# RS-485.net
KiCad netlist of a schematic drawn in Altium Designer
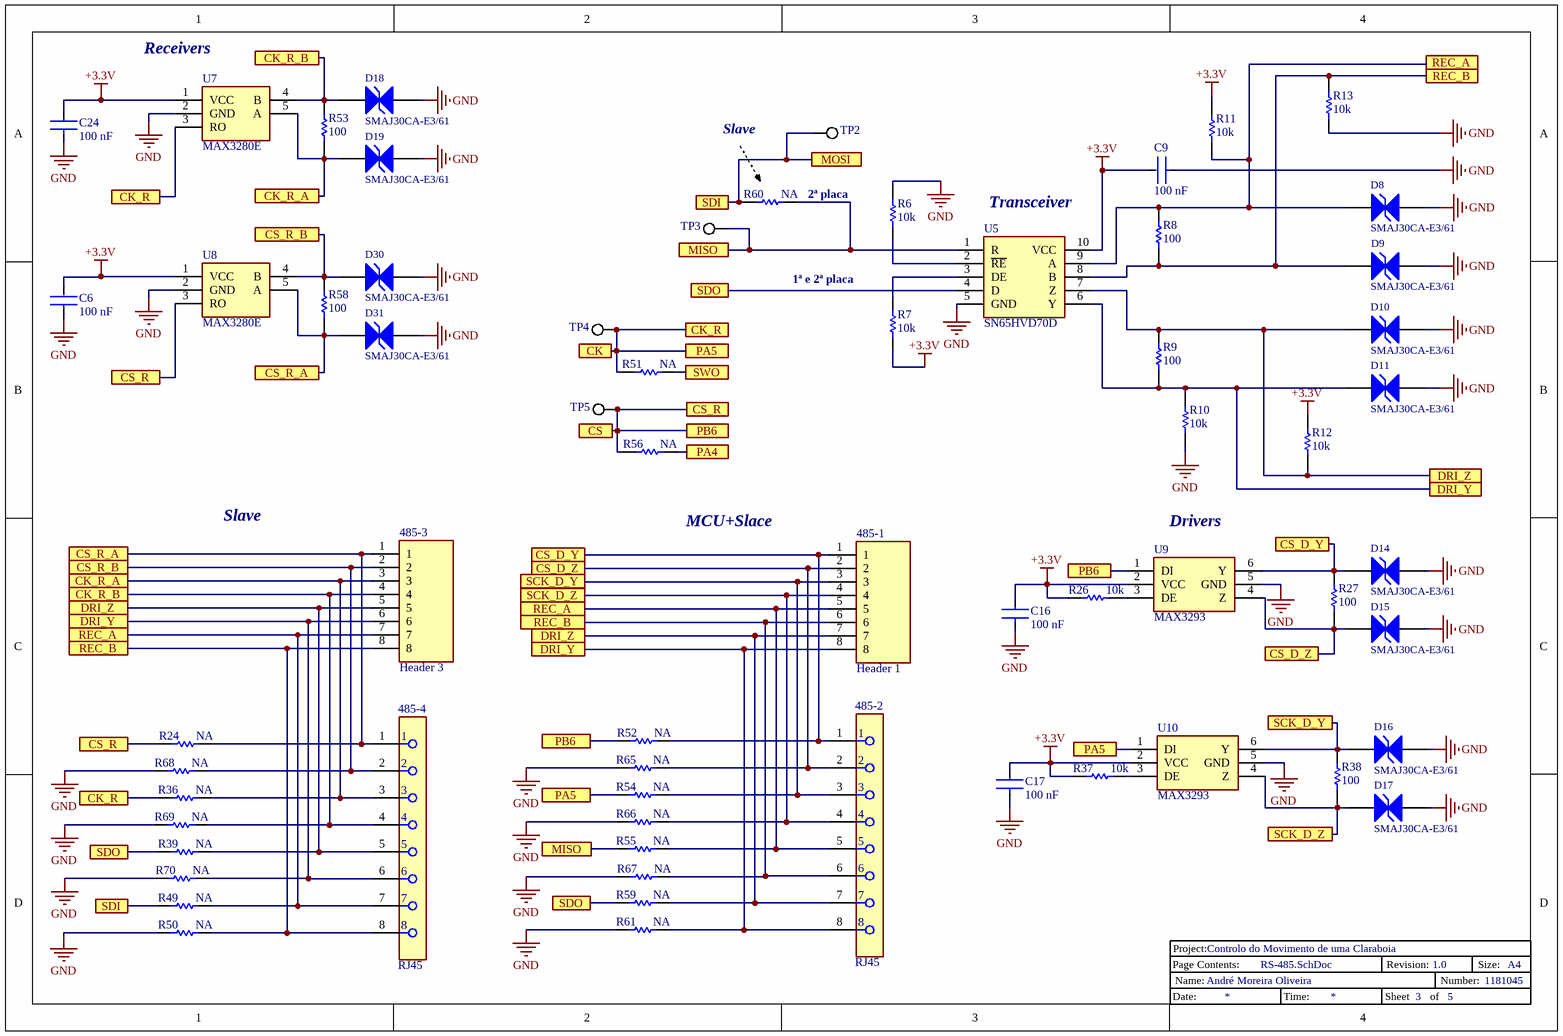
[diagram p0: RS-485.SchDoc]

(export (version "E")
  (design (tool "Eeschema 10.0.6"))
  (components
    (comp (ref "485-1")
      (value "Header 1")
      (footprint "SamacSys:SHDRRA8W64P0X250_1X8_2250X820X420P")
      (description "Conector Femea 1*8 90 graus")
      (fields (field (name "MANUFACTURER_PART_NUMBER") "S8B-EH(LF)(SN)"))
      (libsource (lib "*") (part "S8B-EH_LF__SN_"))
    )
    (comp (ref "485-2")
      (value "RJ45")
      (footprint "FP-RJHSE-5080-MFG")
      (description "CONN MOD JACK 8P8C R/A UNSHLD")
      (fields
        (field (name "MANUFACTURER PART NUMBER") "RJHSE-5080")
        (field (name "OCTOPART") "https://octopart.com/rjhse-5080-amphenol-45060")
      )
      (libsource (lib "Altium Content Vault") (part "b0a0b555dd3abf3683e7c330df25cc4"))
    )
    (comp (ref "485-3")
      (value "Header 3")
      (footprint "SamacSys:SHDRRA8W64P0X250_1X8_2250X820X420P")
      (description "Conector Femea 1*8 90 graus")
      (fields (field (name "MANUFACTURER_PART_NUMBER") "S8B-EH(LF)(SN)"))
      (libsource (lib "*") (part "S8B-EH_LF__SN_"))
    )
    (comp (ref "485-4")
      (value "RJ45")
      (footprint "FP-RJHSE-5080-MFG")
      (description "CONN MOD JACK 8P8C R/A UNSHLD")
      (fields
        (field (name "MANUFACTURER PART NUMBER") "RJHSE-5080")
        (field (name "OCTOPART") "https://octopart.com/rjhse-5080-amphenol-45060")
      )
      (libsource (lib "Altium Content Vault") (part "b0a0b555dd3abf3683e7c330df25cc4"))
    )
    (comp (ref "C6")
      (value "100 nF")
      (footprint "FP-CC0603-DA-MFG")
      (description "CAP CER 0.1UF 50V X7R 0603")
      (fields (field (name "MANUFACTURER") "YAGEO") (field (name "VOLTAGE") "50 V"))
      (libsource (lib "Altium Content Vault") (part "11868f565c42a9108669ba33697ecf6"))
    )
    (comp (ref "C9")
      (value "100 nF")
      (footprint "FP-CC0603-DA-MFG")
      (description "CAP CER 0.1UF 50V X7R 0603")
      (fields (field (name "MANUFACTURER") "YAGEO") (field (name "VOLTAGE") "50 V"))
      (libsource (lib "Altium Content Vault") (part "11868f565c42a9108669ba33697ecf6"))
    )
    (comp (ref "C16")
      (value "100 nF")
      (footprint "FP-CC0603-DA-MFG")
      (description "CAP CER 0.1UF 50V X7R 0603")
      (fields (field (name "MANUFACTURER") "YAGEO") (field (name "VOLTAGE") "50 V"))
      (libsource (lib "Altium Content Vault") (part "11868f565c42a9108669ba33697ecf6"))
    )
    (comp (ref "C17")
      (value "100 nF")
      (footprint "FP-CC0603-DA-MFG")
      (description "CAP CER 0.1UF 50V X7R 0603")
      (fields (field (name "MANUFACTURER") "YAGEO") (field (name "VOLTAGE") "50 V"))
      (libsource (lib "Altium Content Vault") (part "11868f565c42a9108669ba33697ecf6"))
    )
    (comp (ref "C24")
      (value "100 nF")
      (footprint "FP-CC0603-DA-MFG")
      (description "CAP CER 0.1UF 50V X7R 0603")
      (fields (field (name "MANUFACTURER") "YAGEO") (field (name "VOLTAGE") "50 V"))
      (libsource (lib "Altium Content Vault") (part "11868f565c42a9108669ba33697ecf6"))
    )
    (comp (ref "D8")
      (value "SMAJ30CA-E3/61")
      (footprint "VISH-DO-214AC-2_L")
      (fields (field (name "MANUFACTURER") "Vishay Semiconductor"))
      (libsource (lib "Altium Content Vault") (part "VISH-A1A2-2"))
    )
    (comp (ref "D9")
      (value "SMAJ30CA-E3/61")
      (footprint "VISH-DO-214AC-2_L")
      (fields (field (name "MANUFACTURER") "Vishay Semiconductor"))
      (libsource (lib "Altium Content Vault") (part "VISH-A1A2-2"))
    )
    (comp (ref "D10")
      (value "SMAJ30CA-E3/61")
      (footprint "VISH-DO-214AC-2_L")
      (fields (field (name "MANUFACTURER") "Vishay Semiconductor"))
      (libsource (lib "Altium Content Vault") (part "VISH-A1A2-2"))
    )
    (comp (ref "D11")
      (value "SMAJ30CA-E3/61")
      (footprint "VISH-DO-214AC-2_L")
      (fields (field (name "MANUFACTURER") "Vishay Semiconductor"))
      (libsource (lib "Altium Content Vault") (part "VISH-A1A2-2"))
    )
    (comp (ref "D14")
      (value "SMAJ30CA-E3/61")
      (footprint "VISH-DO-214AC-2_L")
      (fields (field (name "MANUFACTURER") "Vishay Semiconductor"))
      (libsource (lib "Altium Content Vault") (part "VISH-A1A2-2"))
    )
    (comp (ref "D15")
      (value "SMAJ30CA-E3/61")
      (footprint "VISH-DO-214AC-2_L")
      (fields (field (name "MANUFACTURER") "Vishay Semiconductor"))
      (libsource (lib "Altium Content Vault") (part "VISH-A1A2-2"))
    )
    (comp (ref "D16")
      (value "SMAJ30CA-E3/61")
      (footprint "VISH-DO-214AC-2_L")
      (fields (field (name "MANUFACTURER") "Vishay Semiconductor"))
      (libsource (lib "Altium Content Vault") (part "VISH-A1A2-2"))
    )
    (comp (ref "D17")
      (value "SMAJ30CA-E3/61")
      (footprint "VISH-DO-214AC-2_L")
      (fields (field (name "MANUFACTURER") "Vishay Semiconductor"))
      (libsource (lib "Altium Content Vault") (part "VISH-A1A2-2"))
    )
    (comp (ref "D18")
      (value "SMAJ30CA-E3/61")
      (footprint "VISH-DO-214AC-2_L")
      (fields (field (name "MANUFACTURER") "Vishay Semiconductor"))
      (libsource (lib "Altium Content Vault") (part "VISH-A1A2-2"))
    )
    (comp (ref "D19")
      (value "SMAJ30CA-E3/61")
      (footprint "VISH-DO-214AC-2_L")
      (fields (field (name "MANUFACTURER") "Vishay Semiconductor"))
      (libsource (lib "Altium Content Vault") (part "VISH-A1A2-2"))
    )
    (comp (ref "D30")
      (value "SMAJ30CA-E3/61")
      (footprint "VISH-DO-214AC-2_L")
      (fields (field (name "MANUFACTURER") "Vishay Semiconductor"))
      (libsource (lib "Altium Content Vault") (part "VISH-A1A2-2"))
    )
    (comp (ref "D31")
      (value "SMAJ30CA-E3/61")
      (footprint "VISH-DO-214AC-2_L")
      (fields (field (name "MANUFACTURER") "Vishay Semiconductor"))
      (libsource (lib "Altium Content Vault") (part "VISH-A1A2-2"))
    )
    (comp (ref "R6")
      (value "10k")
      (footprint "RESC1608X55X25ML10T15")
      (description "Resistor, 10 kOhm, +/- 5%, 100 mW, -55 to 155 degC, 0603 (1608 Metric), RoHS, Tape and Reel")
      (fields (field (name "MANUFACTURER") "Yageo") (field (name "TOLERANCE") "5%"))
      (libsource (lib "Altium Content Vault") (part "RES-2"))
    )
    (comp (ref "R7")
      (value "10k")
      (footprint "RESC1608X55X25ML10T15")
      (description "Resistor, 10 kOhm, +/- 5%, 100 mW, -55 to 155 degC, 0603 (1608 Metric), RoHS, Tape and Reel")
      (fields (field (name "MANUFACTURER") "Yageo") (field (name "TOLERANCE") "5%"))
      (libsource (lib "Altium Content Vault") (part "RES-2"))
    )
    (comp (ref "R8")
      (value "100")
      (footprint "RESC1608X55X25ML10T15")
      (description "Chip Resistor, 100 Ohm, +/- 5%, 0.1 W, -55 to 155 degC, 0603 (1608 Metric), RoHS, Tape and Reel")
      (fields (field (name "TOLERANCE") "5%") (field (name "MANUFACTURER") "Yageo"))
      (libsource (lib "Altium Content Vault") (part "RES-2"))
    )
    (comp (ref "R9")
      (value "100")
      (footprint "RESC1608X55X25ML10T15")
      (description "Chip Resistor, 100 Ohm, +/- 5%, 0.1 W, -55 to 155 degC, 0603 (1608 Metric), RoHS, Tape and Reel")
      (fields (field (name "TOLERANCE") "5%") (field (name "MANUFACTURER") "Yageo"))
      (libsource (lib "Altium Content Vault") (part "RES-2"))
    )
    (comp (ref "R10")
      (value "10k")
      (footprint "RESC1608X55X25ML10T15")
      (description "Resistor, 10 kOhm, +/- 5%, 100 mW, -55 to 155 degC, 0603 (1608 Metric), RoHS, Tape and Reel")
      (fields (field (name "MANUFACTURER") "Yageo") (field (name "TOLERANCE") "5%"))
      (libsource (lib "Altium Content Vault") (part "RES-2"))
    )
    (comp (ref "R11")
      (value "10k")
      (footprint "RESC1608X55X25ML10T15")
      (description "Resistor, 10 kOhm, +/- 5%, 100 mW, -55 to 155 degC, 0603 (1608 Metric), RoHS, Tape and Reel")
      (fields (field (name "MANUFACTURER") "Yageo") (field (name "TOLERANCE") "5%"))
      (libsource (lib "Altium Content Vault") (part "RES-2"))
    )
    (comp (ref "R12")
      (value "10k")
      (footprint "RESC1608X55X25ML10T15")
      (description "Resistor, 10 kOhm, +/- 5%, 100 mW, -55 to 155 degC, 0603 (1608 Metric), RoHS, Tape and Reel")
      (fields (field (name "MANUFACTURER") "Yageo") (field (name "TOLERANCE") "5%"))
      (libsource (lib "Altium Content Vault") (part "RES-2"))
    )
    (comp (ref "R13")
      (value "10k")
      (footprint "RESC1608X55X25ML10T15")
      (description "Resistor, 10 kOhm, +/- 5%, 100 mW, -55 to 155 degC, 0603 (1608 Metric), RoHS, Tape and Reel")
      (fields (field (name "MANUFACTURER") "Yageo") (field (name "TOLERANCE") "5%"))
      (libsource (lib "Altium Content Vault") (part "RES-2"))
    )
    (comp (ref "R24")
      (value "NA")
      (footprint "RESC1608X55X25ML10T15")
      (description "Chip Resistor, 0 Ohm, +/- 5%, 0.1 W, -55 to 155 degC, 0603 (1608 Metric), RoHS, Tape and Reel")
      (fields (field (name "TOLERANCE") "5%") (field (name "MANUFACTURER") "Yageo"))
      (libsource (lib "Altium Content Vault") (part "RES-2"))
    )
    (comp (ref "R26")
      (value "10k")
      (footprint "RESC1608X55X25ML10T15")
      (description "Resistor, 10 kOhm, +/- 5%, 100 mW, -55 to 155 degC, 0603 (1608 Metric), RoHS, Tape and Reel")
      (fields (field (name "MANUFACTURER") "Yageo") (field (name "TOLERANCE") "5%"))
      (libsource (lib "") (part "RES-2_1"))
    )
    (comp (ref "R27")
      (value "100")
      (footprint "RESC1608X55X25ML10T15")
      (description "Chip Resistor, 100 Ohm, +/- 5%, 0.1 W, -55 to 155 degC, 0603 (1608 Metric), RoHS, Tape and Reel")
      (fields (field (name "TOLERANCE") "5%") (field (name "MANUFACTURER") "Yageo"))
      (libsource (lib "Altium Content Vault") (part "RES-2"))
    )
    (comp (ref "R36")
      (value "NA")
      (footprint "RESC1608X55X25ML10T15")
      (description "Chip Resistor, 0 Ohm, +/- 5%, 0.1 W, -55 to 155 degC, 0603 (1608 Metric), RoHS, Tape and Reel")
      (fields (field (name "TOLERANCE") "5%") (field (name "MANUFACTURER") "Yageo"))
      (libsource (lib "Altium Content Vault") (part "RES-2"))
    )
    (comp (ref "R37")
      (value "10k")
      (footprint "RESC1608X55X25ML10T15")
      (description "Resistor, 10 kOhm, +/- 5%, 100 mW, -55 to 155 degC, 0603 (1608 Metric), RoHS, Tape and Reel")
      (fields (field (name "MANUFACTURER") "Yageo") (field (name "TOLERANCE") "5%"))
      (libsource (lib "") (part "RES-2_1"))
    )
    (comp (ref "R38")
      (value "100")
      (footprint "RESC1608X55X25ML10T15")
      (description "Chip Resistor, 100 Ohm, +/- 5%, 0.1 W, -55 to 155 degC, 0603 (1608 Metric), RoHS, Tape and Reel")
      (fields (field (name "TOLERANCE") "5%") (field (name "MANUFACTURER") "Yageo"))
      (libsource (lib "Altium Content Vault") (part "RES-2"))
    )
    (comp (ref "R39")
      (value "NA")
      (footprint "RESC1608X55X25ML10T15")
      (description "Chip Resistor, 0 Ohm, +/- 5%, 0.1 W, -55 to 155 degC, 0603 (1608 Metric), RoHS, Tape and Reel")
      (fields (field (name "TOLERANCE") "5%") (field (name "MANUFACTURER") "Yageo"))
      (libsource (lib "Altium Content Vault") (part "RES-2"))
    )
    (comp (ref "R49")
      (value "NA")
      (footprint "RESC1608X55X25ML10T15")
      (description "Chip Resistor, 0 Ohm, +/- 5%, 0.1 W, -55 to 155 degC, 0603 (1608 Metric), RoHS, Tape and Reel")
      (fields (field (name "TOLERANCE") "5%") (field (name "MANUFACTURER") "Yageo"))
      (libsource (lib "Altium Content Vault") (part "RES-2"))
    )
    (comp (ref "R50")
      (value "NA")
      (footprint "RESC1608X55X25ML10T15")
      (description "Chip Resistor, 0 Ohm, +/- 5%, 0.1 W, -55 to 155 degC, 0603 (1608 Metric), RoHS, Tape and Reel")
      (fields (field (name "TOLERANCE") "5%") (field (name "MANUFACTURER") "Yageo"))
      (libsource (lib "Altium Content Vault") (part "RES-2"))
    )
    (comp (ref "R51")
      (value "NA")
      (footprint "RESC1608X55X25ML10T15")
      (description "Chip Resistor, 0 Ohm, +/- 5%, 0.1 W, -55 to 155 degC, 0603 (1608 Metric), RoHS, Tape and Reel")
      (fields (field (name "TOLERANCE") "5%") (field (name "MANUFACTURER") "Yageo"))
      (libsource (lib "Altium Content Vault") (part "RES-2"))
    )
    (comp (ref "R52")
      (value "NA")
      (footprint "RESC1608X55X25ML10T15")
      (description "Chip Resistor, 0 Ohm, +/- 5%, 0.1 W, -55 to 155 degC, 0603 (1608 Metric), RoHS, Tape and Reel")
      (fields (field (name "TOLERANCE") "5%") (field (name "MANUFACTURER") "Yageo"))
      (libsource (lib "Altium Content Vault") (part "RES-2"))
    )
    (comp (ref "R53")
      (value "100")
      (footprint "RESC1608X55X25ML10T15")
      (description "Chip Resistor, 100 Ohm, +/- 5%, 0.1 W, -55 to 155 degC, 0603 (1608 Metric), RoHS, Tape and Reel")
      (fields (field (name "TOLERANCE") "5%") (field (name "MANUFACTURER") "Yageo"))
      (libsource (lib "Altium Content Vault") (part "RES-2"))
    )
    (comp (ref "R54")
      (value "NA")
      (footprint "RESC1608X55X25ML10T15")
      (description "Chip Resistor, 0 Ohm, +/- 5%, 0.1 W, -55 to 155 degC, 0603 (1608 Metric), RoHS, Tape and Reel")
      (fields (field (name "TOLERANCE") "5%") (field (name "MANUFACTURER") "Yageo"))
      (libsource (lib "Altium Content Vault") (part "RES-2"))
    )
    (comp (ref "R55")
      (value "NA")
      (footprint "RESC1608X55X25ML10T15")
      (description "Chip Resistor, 0 Ohm, +/- 5%, 0.1 W, -55 to 155 degC, 0603 (1608 Metric), RoHS, Tape and Reel")
      (fields (field (name "TOLERANCE") "5%") (field (name "MANUFACTURER") "Yageo"))
      (libsource (lib "Altium Content Vault") (part "RES-2"))
    )
    (comp (ref "R56")
      (value "NA")
      (footprint "RESC1608X55X25ML10T15")
      (description "Chip Resistor, 0 Ohm, +/- 5%, 0.1 W, -55 to 155 degC, 0603 (1608 Metric), RoHS, Tape and Reel")
      (fields (field (name "TOLERANCE") "5%") (field (name "MANUFACTURER") "Yageo"))
      (libsource (lib "Altium Content Vault") (part "RES-2"))
    )
    (comp (ref "R58")
      (value "100")
      (footprint "RESC1608X55X25ML10T15")
      (description "Chip Resistor, 100 Ohm, +/- 5%, 0.1 W, -55 to 155 degC, 0603 (1608 Metric), RoHS, Tape and Reel")
      (fields (field (name "TOLERANCE") "5%") (field (name "MANUFACTURER") "Yageo"))
      (libsource (lib "Altium Content Vault") (part "RES-2"))
    )
    (comp (ref "R59")
      (value "NA")
      (footprint "RESC1608X55X25ML10T15")
      (description "Chip Resistor, 0 Ohm, +/- 5%, 0.1 W, -55 to 155 degC, 0603 (1608 Metric), RoHS, Tape and Reel")
      (fields (field (name "TOLERANCE") "5%") (field (name "MANUFACTURER") "Yageo"))
      (libsource (lib "Altium Content Vault") (part "RES-2"))
    )
    (comp (ref "R60")
      (value "NA")
      (footprint "RESC1608X55X25ML10T15")
      (description "Chip Resistor, 0 Ohm, +/- 5%, 0.1 W, -55 to 155 degC, 0603 (1608 Metric), RoHS, Tape and Reel")
      (fields (field (name "TOLERANCE") "5%") (field (name "MANUFACTURER") "Yageo"))
      (libsource (lib "Altium Content Vault") (part "RES-2"))
    )
    (comp (ref "R61")
      (value "NA")
      (footprint "RESC1608X55X25ML10T15")
      (description "Chip Resistor, 0 Ohm, +/- 5%, 0.1 W, -55 to 155 degC, 0603 (1608 Metric), RoHS, Tape and Reel")
      (fields (field (name "TOLERANCE") "5%") (field (name "MANUFACTURER") "Yageo"))
      (libsource (lib "Altium Content Vault") (part "RES-2"))
    )
    (comp (ref "R65")
      (value "NA")
      (footprint "RESC1608X55X25ML10T15")
      (description "Chip Resistor, 0 Ohm, +/- 5%, 0.1 W, -55 to 155 degC, 0603 (1608 Metric), RoHS, Tape and Reel")
      (fields (field (name "TOLERANCE") "5%") (field (name "MANUFACTURER") "Yageo"))
      (libsource (lib "Altium Content Vault") (part "RES-2"))
    )
    (comp (ref "R66")
      (value "NA")
      (footprint "RESC1608X55X25ML10T15")
      (description "Chip Resistor, 0 Ohm, +/- 5%, 0.1 W, -55 to 155 degC, 0603 (1608 Metric), RoHS, Tape and Reel")
      (fields (field (name "TOLERANCE") "5%") (field (name "MANUFACTURER") "Yageo"))
      (libsource (lib "Altium Content Vault") (part "RES-2"))
    )
    (comp (ref "R67")
      (value "NA")
      (footprint "RESC1608X55X25ML10T15")
      (description "Chip Resistor, 0 Ohm, +/- 5%, 0.1 W, -55 to 155 degC, 0603 (1608 Metric), RoHS, Tape and Reel")
      (fields (field (name "TOLERANCE") "5%") (field (name "MANUFACTURER") "Yageo"))
      (libsource (lib "Altium Content Vault") (part "RES-2"))
    )
    (comp (ref "R68")
      (value "NA")
      (footprint "RESC1608X55X25ML10T15")
      (description "Chip Resistor, 0 Ohm, +/- 5%, 0.1 W, -55 to 155 degC, 0603 (1608 Metric), RoHS, Tape and Reel")
      (fields (field (name "TOLERANCE") "5%") (field (name "MANUFACTURER") "Yageo"))
      (libsource (lib "Altium Content Vault") (part "RES-2"))
    )
    (comp (ref "R69")
      (value "NA")
      (footprint "RESC1608X55X25ML10T15")
      (description "Chip Resistor, 0 Ohm, +/- 5%, 0.1 W, -55 to 155 degC, 0603 (1608 Metric), RoHS, Tape and Reel")
      (fields (field (name "TOLERANCE") "5%") (field (name "MANUFACTURER") "Yageo"))
      (libsource (lib "Altium Content Vault") (part "RES-2"))
    )
    (comp (ref "R70")
      (value "NA")
      (footprint "RESC1608X55X25ML10T15")
      (description "Chip Resistor, 0 Ohm, +/- 5%, 0.1 W, -55 to 155 degC, 0603 (1608 Metric), RoHS, Tape and Reel")
      (fields (field (name "TOLERANCE") "5%") (field (name "MANUFACTURER") "Yageo"))
      (libsource (lib "Altium Content Vault") (part "RES-2"))
    )
    (comp (ref "Title_Block_3") (value "Title_Block") (libsource (lib "Title_Block") (part "Title_Block")))
    (comp (ref "TP2")
      (value "5000")
      (footprint "KSTN-5002")
      (description "Test Point, White, 1-Pin THD, RoHS, Bulk")
      (fields (field (name "MANUFACTURER") "KeystoneElectronics"))
      (libsource (lib "Altium Content Vault") (part "KSTN-TP-5002"))
    )
    (comp (ref "TP3")
      (value "5000")
      (footprint "KSTN-5002")
      (description "Test Point, White, 1-Pin THD, RoHS, Bulk")
      (fields (field (name "MANUFACTURER") "KeystoneElectronics"))
      (libsource (lib "Altium Content Vault") (part "KSTN-TP-5002"))
    )
    (comp (ref "TP4")
      (value "5000")
      (footprint "KSTN-5002")
      (description "Test Point, White, 1-Pin THD, RoHS, Bulk")
      (fields (field (name "MANUFACTURER") "KeystoneElectronics"))
      (libsource (lib "Altium Content Vault") (part "KSTN-TP-5002"))
    )
    (comp (ref "TP5")
      (value "5000")
      (footprint "KSTN-5002")
      (description "Test Point, White, 1-Pin THD, RoHS, Bulk")
      (fields (field (name "MANUFACTURER") "KeystoneElectronics"))
      (libsource (lib "Altium Content Vault") (part "KSTN-TP-5002"))
    )
    (comp (ref "U5")
      (value "SN65HVD70D")
      (footprint "SamacSys:SOP50P490X110-10N")
      (description "Integrated Circuit")
      (fields
        (field (name "MANUFACTURER_PART_NUMBER") "SN65HVD70DGS")
        (field (name "MOUSER PART NUMBER") "595-SN65HVD70DGS")
      )
      (libsource (lib "*") (part "SN65HVD70DGS"))
    )
    (comp (ref "U7")
      (value "MAX3280E")
      (footprint "SamacSys:SOT95P280X145-5N")
      (description "Integrated Circuit")
      (fields
        (field (name "MANUFACTURER_PART_NUMBER") "MAX3280EAUK/V+T")
        (field (name "MOUSER PART NUMBER") "700-MAX3280EAUK/V+T")
      )
      (libsource (lib "*") (part "MAX3280EAUK_V+T"))
    )
    (comp (ref "U8")
      (value "MAX3280E")
      (footprint "SamacSys:SOT95P280X145-5N")
      (description "Integrated Circuit")
      (fields
        (field (name "MANUFACTURER_PART_NUMBER") "MAX3280EAUK/V+T")
        (field (name "MOUSER PART NUMBER") "700-MAX3280EAUK/V+T")
      )
      (libsource (lib "*") (part "MAX3280EAUK_V+T"))
    )
    (comp (ref "U9")
      (value "MAX3293")
      (footprint "SamacSys:SOT95P280X145-6N")
      (description "Integrated Circuit")
      (fields
        (field (name "MANUFACTURER_PART_NUMBER") "MAX3293AUT+T")
        (field (name "MOUSER PART NUMBER") "700-MAX3293AUTT")
      )
      (libsource (lib "*") (part "MAX3293AUT+T"))
    )
    (comp (ref "U10")
      (value "MAX3293")
      (footprint "SamacSys:SOT95P280X145-6N")
      (description "Integrated Circuit")
      (fields
        (field (name "MANUFACTURER_PART_NUMBER") "MAX3293AUT+T")
        (field (name "MOUSER PART NUMBER") "700-MAX3293AUTT")
      )
      (libsource (lib "*") (part "MAX3293AUT+T"))
    )
  )
  (nets
    (net (code "1") (name "+3.3V") (class "Default")
      (node (ref "C16") (pin "2") (pinfunction "2_2") (pintype "passive"))
      (node (ref "C17") (pin "2") (pinfunction "2_2") (pintype "passive"))
      (node (ref "C24") (pin "2") (pinfunction "2_2") (pintype "passive"))
      (node (ref "C6") (pin "2") (pinfunction "2_2") (pintype "passive"))
      (node (ref "C9") (pin "2") (pinfunction "2_2") (pintype "passive"))
      (node (ref "R11") (pin "2") (pinfunction "2_2") (pintype "passive"))
      (node (ref "R12") (pin "2") (pinfunction "2_2") (pintype "passive"))
      (node (ref "R26") (pin "1") (pinfunction "1_1") (pintype "passive"))
      (node (ref "R37") (pin "1") (pinfunction "1_1") (pintype "passive"))
      (node (ref "R7") (pin "1") (pinfunction "1_1") (pintype "passive"))
      (node (ref "U10") (pin "2") (pinfunction "VCC_2") (pintype "passive"))
      (node (ref "U5") (pin "10") (pinfunction "VCC_10") (pintype "passive"))
      (node (ref "U7") (pin "1") (pinfunction "VCC_1") (pintype "passive"))
      (node (ref "U8") (pin "1") (pinfunction "VCC_1") (pintype "passive"))
      (node (ref "U9") (pin "2") (pinfunction "VCC_2") (pintype "passive"))
    )
    (net (code "2") (name "/CK") (class "Default")
      (node (ref "R36") (pin "1") (pinfunction "1_1") (pintype "passive"))
      (node (ref "R51") (pin "1") (pinfunction "1_1") (pintype "passive"))
      (node (ref "R54") (pin "1") (pinfunction "1_1") (pintype "passive"))
      (node (ref "TP4") (pin "1") (pintype "passive"))
      (node (ref "U10") (pin "1") (pinfunction "DI_1") (pintype "passive"))
      (node (ref "U7") (pin "3") (pinfunction "RO_3") (pintype "passive"))
    )
    (net (code "3") (name "/CK_R_A") (class "Default")
      (node (ref "485-3") (pin "3") (pinfunction "3_3") (pintype "passive"))
      (node (ref "485-4") (pin "3") (pinfunction "3_3") (pintype "passive"))
      (node (ref "D19") (pin "2") (pinfunction "A2_2") (pintype "passive"))
      (node (ref "R36") (pin "2") (pinfunction "2_2") (pintype "passive"))
      (node (ref "R53") (pin "1") (pinfunction "1_1") (pintype "passive"))
      (node (ref "U7") (pin "5") (pinfunction "A_5") (pintype "passive"))
    )
    (net (code "4") (name "/CK_R_B") (class "Default")
      (node (ref "485-3") (pin "4") (pinfunction "4_4") (pintype "passive"))
      (node (ref "485-4") (pin "4") (pinfunction "4_4") (pintype "passive"))
      (node (ref "D18") (pin "2") (pinfunction "A2_2") (pintype "passive"))
      (node (ref "R53") (pin "2") (pinfunction "2_2") (pintype "passive"))
      (node (ref "R69") (pin "2") (pinfunction "2_2") (pintype "passive"))
      (node (ref "U7") (pin "4") (pinfunction "B_4") (pintype "passive"))
    )
    (net (code "5") (name "/CS") (class "Default")
      (node (ref "R24") (pin "1") (pinfunction "1_1") (pintype "passive"))
      (node (ref "R52") (pin "1") (pinfunction "1_1") (pintype "passive"))
      (node (ref "R56") (pin "1") (pinfunction "1_1") (pintype "passive"))
      (node (ref "TP5") (pin "1") (pintype "passive"))
      (node (ref "U8") (pin "3") (pinfunction "RO_3") (pintype "passive"))
      (node (ref "U9") (pin "1") (pinfunction "DI_1") (pintype "passive"))
    )
    (net (code "6") (name "/CS_D_Y") (class "Default")
      (node (ref "485-1") (pin "1") (pinfunction "1_1") (pintype "passive"))
      (node (ref "485-2") (pin "1") (pinfunction "1_1") (pintype "passive"))
      (node (ref "D14") (pin "2") (pinfunction "A2_2") (pintype "passive"))
      (node (ref "R27") (pin "2") (pinfunction "2_2") (pintype "passive"))
      (node (ref "R52") (pin "2") (pinfunction "2_2") (pintype "passive"))
      (node (ref "U9") (pin "6") (pinfunction "Y_6") (pintype "passive"))
    )
    (net (code "7") (name "/CS_D_Z") (class "Default")
      (node (ref "485-1") (pin "2") (pinfunction "2_2") (pintype "passive"))
      (node (ref "485-2") (pin "2") (pinfunction "2_2") (pintype "passive"))
      (node (ref "D15") (pin "2") (pinfunction "A2_2") (pintype "passive"))
      (node (ref "R27") (pin "1") (pinfunction "1_1") (pintype "passive"))
      (node (ref "R65") (pin "2") (pinfunction "2_2") (pintype "passive"))
      (node (ref "U9") (pin "4") (pinfunction "Z_4") (pintype "passive"))
    )
    (net (code "8") (name "/CS_R_A") (class "Default")
      (node (ref "485-3") (pin "1") (pinfunction "1_1") (pintype "passive"))
      (node (ref "485-4") (pin "1") (pinfunction "1_1") (pintype "passive"))
      (node (ref "D31") (pin "2") (pinfunction "A2_2") (pintype "passive"))
      (node (ref "R24") (pin "2") (pinfunction "2_2") (pintype "passive"))
      (node (ref "R58") (pin "1") (pinfunction "1_1") (pintype "passive"))
      (node (ref "U8") (pin "5") (pinfunction "A_5") (pintype "passive"))
    )
    (net (code "9") (name "/CS_R_B") (class "Default")
      (node (ref "485-3") (pin "2") (pinfunction "2_2") (pintype "passive"))
      (node (ref "485-4") (pin "2") (pinfunction "2_2") (pintype "passive"))
      (node (ref "D30") (pin "2") (pinfunction "A2_2") (pintype "passive"))
      (node (ref "R58") (pin "2") (pinfunction "2_2") (pintype "passive"))
      (node (ref "R68") (pin "2") (pinfunction "2_2") (pintype "passive"))
      (node (ref "U8") (pin "4") (pinfunction "B_4") (pintype "passive"))
    )
    (net (code "10") (name "/DRI_Y") (class "Default")
      (node (ref "485-1") (pin "8") (pinfunction "8_8") (pintype "passive"))
      (node (ref "485-2") (pin "8") (pinfunction "8_8") (pintype "passive"))
      (node (ref "485-3") (pin "6") (pinfunction "6_6") (pintype "passive"))
      (node (ref "485-4") (pin "6") (pinfunction "6_6") (pintype "passive"))
      (node (ref "D11") (pin "2") (pinfunction "A2_2") (pintype "passive"))
      (node (ref "R10") (pin "2") (pinfunction "2_2") (pintype "passive"))
      (node (ref "R61") (pin "2") (pinfunction "2_2") (pintype "passive"))
      (node (ref "R70") (pin "2") (pinfunction "2_2") (pintype "passive"))
      (node (ref "R9") (pin "1") (pinfunction "1_1") (pintype "passive"))
      (node (ref "U5") (pin "6") (pinfunction "Y_6") (pintype "passive"))
    )
    (net (code "11") (name "/DRI_Z") (class "Default")
      (node (ref "485-1") (pin "7") (pinfunction "7_7") (pintype "passive"))
      (node (ref "485-2") (pin "7") (pinfunction "7_7") (pintype "passive"))
      (node (ref "485-3") (pin "5") (pinfunction "5_5") (pintype "passive"))
      (node (ref "485-4") (pin "5") (pinfunction "5_5") (pintype "passive"))
      (node (ref "D10") (pin "2") (pinfunction "A2_2") (pintype "passive"))
      (node (ref "R12") (pin "1") (pinfunction "1_1") (pintype "passive"))
      (node (ref "R39") (pin "2") (pinfunction "2_2") (pintype "passive"))
      (node (ref "R59") (pin "2") (pinfunction "2_2") (pintype "passive"))
      (node (ref "R9") (pin "2") (pinfunction "2_2") (pintype "passive"))
      (node (ref "U5") (pin "7") (pinfunction "Z_7") (pintype "passive"))
    )
    (net (code "12") (name "/MISO") (class "Default")
      (node (ref "R55") (pin "1") (pinfunction "1_1") (pintype "passive"))
      (node (ref "R60") (pin "2") (pinfunction "2_2") (pintype "passive"))
      (node (ref "TP3") (pin "1") (pintype "passive"))
      (node (ref "U5") (pin "1") (pinfunction "R_1") (pintype "passive"))
    )
    (net (code "13") (name "/MOSI") (class "Default")
      (node (ref "R49") (pin "1") (pinfunction "1_1") (pintype "passive"))
      (node (ref "R60") (pin "1") (pinfunction "1_1") (pintype "passive"))
      (node (ref "TP2") (pin "1") (pintype "passive"))
    )
    (net (code "14") (name "/PA4") (class "Default")
      (node (ref "R56") (pin "2") (pinfunction "2_2") (pintype "passive"))
    )
    (net (code "15") (name "/REC_A") (class "Default")
      (node (ref "485-1") (pin "5") (pinfunction "5_5") (pintype "passive"))
      (node (ref "485-2") (pin "5") (pinfunction "5_5") (pintype "passive"))
      (node (ref "485-3") (pin "7") (pinfunction "7_7") (pintype "passive"))
      (node (ref "485-4") (pin "7") (pinfunction "7_7") (pintype "passive"))
      (node (ref "D8") (pin "2") (pinfunction "A2_2") (pintype "passive"))
      (node (ref "R11") (pin "1") (pinfunction "1_1") (pintype "passive"))
      (node (ref "R49") (pin "2") (pinfunction "2_2") (pintype "passive"))
      (node (ref "R55") (pin "2") (pinfunction "2_2") (pintype "passive"))
      (node (ref "R8") (pin "2") (pinfunction "2_2") (pintype "passive"))
      (node (ref "U5") (pin "9") (pinfunction "A_9") (pintype "passive"))
    )
    (net (code "16") (name "/REC_B") (class "Default")
      (node (ref "485-1") (pin "6") (pinfunction "6_6") (pintype "passive"))
      (node (ref "485-2") (pin "6") (pinfunction "6_6") (pintype "passive"))
      (node (ref "485-3") (pin "8") (pinfunction "8_8") (pintype "passive"))
      (node (ref "485-4") (pin "8") (pinfunction "8_8") (pintype "passive"))
      (node (ref "D9") (pin "2") (pinfunction "A2_2") (pintype "passive"))
      (node (ref "R13") (pin "2") (pinfunction "2_2") (pintype "passive"))
      (node (ref "R50") (pin "2") (pinfunction "2_2") (pintype "passive"))
      (node (ref "R67") (pin "2") (pinfunction "2_2") (pintype "passive"))
      (node (ref "R8") (pin "1") (pinfunction "1_1") (pintype "passive"))
      (node (ref "U5") (pin "8") (pinfunction "B_8") (pintype "passive"))
    )
    (net (code "17") (name "/SCK_D_Y") (class "Default")
      (node (ref "485-1") (pin "3") (pinfunction "3_3") (pintype "passive"))
      (node (ref "485-2") (pin "3") (pinfunction "3_3") (pintype "passive"))
      (node (ref "D16") (pin "2") (pinfunction "A2_2") (pintype "passive"))
      (node (ref "R38") (pin "2") (pinfunction "2_2") (pintype "passive"))
      (node (ref "R54") (pin "2") (pinfunction "2_2") (pintype "passive"))
      (node (ref "U10") (pin "6") (pinfunction "Y_6") (pintype "passive"))
    )
    (net (code "18") (name "/SCK_D_Z") (class "Default")
      (node (ref "485-1") (pin "4") (pinfunction "4_4") (pintype "passive"))
      (node (ref "485-2") (pin "4") (pinfunction "4_4") (pintype "passive"))
      (node (ref "D17") (pin "2") (pinfunction "A2_2") (pintype "passive"))
      (node (ref "R38") (pin "1") (pinfunction "1_1") (pintype "passive"))
      (node (ref "R66") (pin "2") (pinfunction "2_2") (pintype "passive"))
      (node (ref "U10") (pin "4") (pinfunction "Z_4") (pintype "passive"))
    )
    (net (code "19") (name "/SDO") (class "Default")
      (node (ref "R39") (pin "1") (pinfunction "1_1") (pintype "passive"))
      (node (ref "R59") (pin "1") (pinfunction "1_1") (pintype "passive"))
      (node (ref "U5") (pin "4") (pinfunction "D_4") (pintype "passive"))
    )
    (net (code "20") (name "/SWO") (class "Default")
      (node (ref "R51") (pin "2") (pinfunction "2_2") (pintype "passive"))
    )
    (net (code "21") (name "GND") (class "Default")
      (node (ref "C16") (pin "1") (pinfunction "1_1") (pintype "passive"))
      (node (ref "C17") (pin "1") (pinfunction "1_1") (pintype "passive"))
      (node (ref "C24") (pin "1") (pinfunction "1_1") (pintype "passive"))
      (node (ref "C6") (pin "1") (pinfunction "1_1") (pintype "passive"))
      (node (ref "C9") (pin "1") (pinfunction "1_1") (pintype "passive"))
      (node (ref "D10") (pin "1") (pinfunction "A1_1") (pintype "passive"))
      (node (ref "D11") (pin "1") (pinfunction "A1_1") (pintype "passive"))
      (node (ref "D14") (pin "1") (pinfunction "A1_1") (pintype "passive"))
      (node (ref "D15") (pin "1") (pinfunction "A1_1") (pintype "passive"))
      (node (ref "D16") (pin "1") (pinfunction "A1_1") (pintype "passive"))
      (node (ref "D17") (pin "1") (pinfunction "A1_1") (pintype "passive"))
      (node (ref "D18") (pin "1") (pinfunction "A1_1") (pintype "passive"))
      (node (ref "D19") (pin "1") (pinfunction "A1_1") (pintype "passive"))
      (node (ref "D30") (pin "1") (pinfunction "A1_1") (pintype "passive"))
      (node (ref "D31") (pin "1") (pinfunction "A1_1") (pintype "passive"))
      (node (ref "D8") (pin "1") (pinfunction "A1_1") (pintype "passive"))
      (node (ref "D9") (pin "1") (pinfunction "A1_1") (pintype "passive"))
      (node (ref "R10") (pin "1") (pinfunction "1_1") (pintype "passive"))
      (node (ref "R13") (pin "1") (pinfunction "1_1") (pintype "passive"))
      (node (ref "R50") (pin "1") (pinfunction "1_1") (pintype "passive"))
      (node (ref "R6") (pin "2") (pinfunction "2_2") (pintype "passive"))
      (node (ref "R61") (pin "1") (pinfunction "1_1") (pintype "passive"))
      (node (ref "R65") (pin "1") (pinfunction "1_1") (pintype "passive"))
      (node (ref "R66") (pin "1") (pinfunction "1_1") (pintype "passive"))
      (node (ref "R67") (pin "1") (pinfunction "1_1") (pintype "passive"))
      (node (ref "R68") (pin "1") (pinfunction "1_1") (pintype "passive"))
      (node (ref "R69") (pin "1") (pinfunction "1_1") (pintype "passive"))
      (node (ref "R70") (pin "1") (pinfunction "1_1") (pintype "passive"))
      (node (ref "U10") (pin "5") (pinfunction "GND_5") (pintype "passive"))
      (node (ref "U5") (pin "5") (pinfunction "GND_5") (pintype "passive"))
      (node (ref "U7") (pin "2") (pinfunction "GND_2") (pintype "passive"))
      (node (ref "U8") (pin "2") (pinfunction "GND_2") (pintype "passive"))
      (node (ref "U9") (pin "5") (pinfunction "GND_5") (pintype "passive"))
    )
    (net (code "22") (name "Net-(U5-DE)") (class "Default")
      (node (ref "R7") (pin "2") (pinfunction "2_2") (pintype "passive"))
      (node (ref "U5") (pin "3") (pinfunction "DE_3") (pintype "passive"))
    )
    (net (code "23") (name "Net-(U5-~{RE})") (class "Default")
      (node (ref "R6") (pin "1") (pinfunction "1_1") (pintype "passive"))
      (node (ref "U5") (pin "2") (pinfunction "~{RE}_2") (pintype "passive"))
    )
    (net (code "24") (name "Net-(U9-DE)") (class "Default")
      (node (ref "R26") (pin "2") (pinfunction "2_2") (pintype "passive"))
      (node (ref "U9") (pin "3") (pinfunction "DE_3") (pintype "passive"))
    )
    (net (code "25") (name "Net-(U10-DE)") (class "Default")
      (node (ref "R37") (pin "2") (pinfunction "2_2") (pintype "passive"))
      (node (ref "U10") (pin "3") (pinfunction "DE_3") (pintype "passive"))
    )
  )
)
